# design.net
KiCad netlist of a schematic drawn in Altium Designer
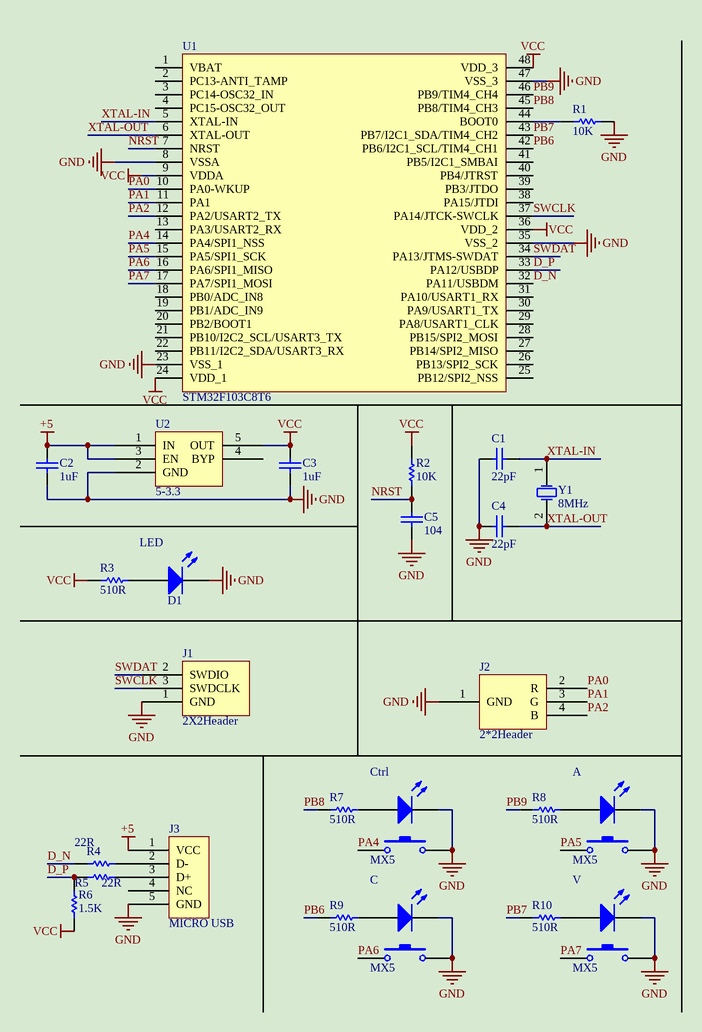
[diagram p0: 原理图.SchDoc]

(export (version "E")
  (design (tool "Eeschema 10.0.6"))
  (components
    (comp (ref "A") (value "MX5") (footprint "Key") (libsource (lib "Keyboard") (part "Key")))
    (comp (ref "C") (value "MX5") (footprint "Key") (libsource (lib "Keyboard") (part "Key")))
    (comp (ref "C1")
      (value "22pF")
      (footprint "LC-1206_C")
      (description "Capacitor")
      (fields (field (name "PUBLISHER") "Altium Limited"))
      (libsource (lib "Keyboard") (part "Capacitor"))
    )
    (comp (ref "C2")
      (value "1uF")
      (footprint "LC-1206_C")
      (description "Capacitor")
      (fields (field (name "PUBLISHER") "Altium Limited"))
      (libsource (lib "Keyboard") (part "Capacitor"))
    )
    (comp (ref "C3")
      (value "1uF")
      (footprint "LC-1206_C")
      (description "Capacitor")
      (fields (field (name "PUBLISHER") "Altium Limited"))
      (libsource (lib "Keyboard") (part "Capacitor"))
    )
    (comp (ref "C4")
      (value "22pF")
      (footprint "LC-1206_C")
      (description "Capacitor")
      (fields (field (name "PUBLISHER") "Altium Limited"))
      (libsource (lib "Keyboard") (part "Capacitor"))
    )
    (comp (ref "C5")
      (value "104")
      (footprint "LC-1206_C")
      (description "Capacitor")
      (fields (field (name "PUBLISHER") "Altium Limited"))
      (libsource (lib "Keyboard") (part "Capacitor"))
    )
    (comp (ref "Ctrl") (value "MX5") (footprint "Key") (libsource (lib "Keyboard") (part "Key")))
    (comp (ref "D1")
      (value "LED")
      (footprint "LC-0603_LED_S3")
      (description "Typical INFRARED GaAs LED")
      (fields (field (name "PUBLISHER") "Altium Limited"))
      (libsource (lib "Keyboard") (part "LED"))
    )
    (comp (ref "J1") (value "2X2Header") (footprint "IDE3") (libsource (lib "Keyboard") (part "J-Link")))
    (comp (ref "J2")
      (value "2*2Header")
      (footprint "IDE4_2.54")
      (libsource (lib "Keyboard") (part "RGB_LED"))
    )
    (comp (ref "J3") (value "MICRO USB") (footprint "Micro_USB") (libsource (lib "Keyboard") (part "USB")))
    (comp (ref "R1")
      (value "10K")
      (footprint "LC-1206_R")
      (description "Resistor")
      (fields (field (name "PUBLISHER") "Altium Limited"))
      (libsource (lib "Keyboard") (part "Resistor"))
    )
    (comp (ref "R2")
      (value "10K")
      (footprint "LC-1206_R")
      (description "Resistor")
      (fields (field (name "PUBLISHER") "Altium Limited"))
      (libsource (lib "Keyboard") (part "Resistor"))
    )
    (comp (ref "R3")
      (value "510R")
      (footprint "LC-1206_R")
      (description "Resistor")
      (fields (field (name "PUBLISHER") "Altium Limited"))
      (libsource (lib "Keyboard") (part "Resistor"))
    )
    (comp (ref "R4")
      (value "22R")
      (footprint "LC-1206_R")
      (description "Resistor")
      (fields (field (name "PUBLISHER") "Altium Limited"))
      (libsource (lib "Keyboard") (part "Resistor"))
    )
    (comp (ref "R5")
      (value "22R")
      (footprint "LC-1206_R")
      (description "Resistor")
      (fields (field (name "PUBLISHER") "Altium Limited"))
      (libsource (lib "Keyboard") (part "Resistor"))
    )
    (comp (ref "R6")
      (value "1.5K")
      (footprint "LC-1206_R")
      (description "Resistor")
      (fields (field (name "PUBLISHER") "Altium Limited"))
      (libsource (lib "Keyboard") (part "Resistor"))
    )
    (comp (ref "R7")
      (value "510R")
      (footprint "LC-1206_R")
      (description "Resistor")
      (fields (field (name "PUBLISHER") "Altium Limited"))
      (libsource (lib "Keyboard") (part "Resistor"))
    )
    (comp (ref "R8")
      (value "510R")
      (footprint "LC-1206_R")
      (description "Resistor")
      (fields (field (name "PUBLISHER") "Altium Limited"))
      (libsource (lib "Keyboard") (part "Resistor"))
    )
    (comp (ref "R9")
      (value "510R")
      (footprint "LC-1206_R")
      (description "Resistor")
      (fields (field (name "PUBLISHER") "Altium Limited"))
      (libsource (lib "Keyboard") (part "Resistor"))
    )
    (comp (ref "R10")
      (value "510R")
      (footprint "LC-1206_R")
      (description "Resistor")
      (fields (field (name "PUBLISHER") "Altium Limited"))
      (libsource (lib "Keyboard") (part "Resistor"))
    )
    (comp (ref "U1")
      (value "STM32F103C8T6")
      (footprint "lqfp48")
      (libsource (lib "Keyboard") (part "STM32F103C8T6"))
    )
    (comp (ref "U2")
      (value "5-3.3")
      (footprint "LC-SOT-23-5")
      (description "SPX3819")
      (libsource (lib "Keyboard") (part "SPX3819"))
    )
    (comp (ref "V") (value "MX5") (footprint "Key") (libsource (lib "Keyboard") (part "Key")))
    (comp (ref "Y1")
      (value "8MHz")
      (footprint "LC-HC-49S")
      (description "Crystal Oscillator")
      (fields (field (name "PUBLISHER") "Altium Limited"))
      (libsource (lib "Keyboard") (part "XTAL"))
    )
  )
  (nets
    (net (code "1") (name "+5") (class "Default")
      (node (ref "C2") (pin "2") (pinfunction "2_2") (pintype "passive"))
      (node (ref "J3") (pin "1") (pinfunction "VCC_1") (pintype "passive"))
      (node (ref "U2") (pin "1") (pinfunction "IN_1") (pintype "passive"))
      (node (ref "U2") (pin "3") (pinfunction "EN_3") (pintype "passive"))
    )
    (net (code "2") (name "/D_N") (class "Default")
      (node (ref "R4") (pin "1") (pinfunction "1_1") (pintype "passive"))
      (node (ref "U1") (pin "32") (pinfunction "PA11/USBDM_32") (pintype "passive"))
    )
    (net (code "3") (name "/D_P") (class "Default")
      (node (ref "R5") (pin "1") (pinfunction "1_1") (pintype "passive"))
      (node (ref "R6") (pin "2") (pinfunction "2_2") (pintype "passive"))
      (node (ref "U1") (pin "33") (pinfunction "PA12/USBDP_33") (pintype "passive"))
    )
    (net (code "4") (name "/NRST") (class "Default")
      (node (ref "C5") (pin "2") (pinfunction "2_2") (pintype "passive"))
      (node (ref "R2") (pin "1") (pinfunction "1_1") (pintype "passive"))
      (node (ref "U1") (pin "7") (pinfunction "NRST_7") (pintype "passive"))
    )
    (net (code "5") (name "/PA0") (class "Default")
      (node (ref "J2") (pin "2") (pinfunction "R_2") (pintype "passive"))
      (node (ref "U1") (pin "10") (pinfunction "PA0-WKUP_10") (pintype "passive"))
    )
    (net (code "6") (name "/PA1") (class "Default")
      (node (ref "J2") (pin "3") (pinfunction "G_3") (pintype "passive"))
      (node (ref "U1") (pin "11") (pinfunction "PA1_11") (pintype "passive"))
    )
    (net (code "7") (name "/PA2") (class "Default")
      (node (ref "J2") (pin "4") (pinfunction "B_4") (pintype "passive"))
      (node (ref "U1") (pin "12") (pinfunction "PA2/USART2_TX_12") (pintype "passive"))
    )
    (net (code "8") (name "/PA4") (class "Default")
      (node (ref "Ctrl") (pin "1") (pinfunction "1_1") (pintype "passive"))
      (node (ref "U1") (pin "14") (pinfunction "PA4/SPI1_NSS_14") (pintype "passive"))
    )
    (net (code "9") (name "/PA5") (class "Default")
      (node (ref "A") (pin "1") (pinfunction "1_1") (pintype "passive"))
      (node (ref "U1") (pin "15") (pinfunction "PA5/SPI1_SCK_15") (pintype "passive"))
    )
    (net (code "10") (name "/PA6") (class "Default")
      (node (ref "C") (pin "1") (pinfunction "1_1") (pintype "passive"))
      (node (ref "U1") (pin "16") (pinfunction "PA6/SPI1_MISO_16") (pintype "passive"))
    )
    (net (code "11") (name "/PA7") (class "Default")
      (node (ref "U1") (pin "17") (pinfunction "PA7/SPI1_MOSI_17") (pintype "passive"))
      (node (ref "V") (pin "1") (pinfunction "1_1") (pintype "passive"))
    )
    (net (code "12") (name "/PB6") (class "Default")
      (node (ref "R9") (pin "1") (pinfunction "1_1") (pintype "passive"))
      (node (ref "U1") (pin "42") (pinfunction "PB6/I2C1_SCL/TIM4_CH1_42") (pintype "passive"))
    )
    (net (code "13") (name "/PB7") (class "Default")
      (node (ref "R10") (pin "1") (pinfunction "1_1") (pintype "passive"))
      (node (ref "U1") (pin "43") (pinfunction "PB7/I2C1_SDA/TIM4_CH2_43") (pintype "passive"))
    )
    (net (code "14") (name "/PB8") (class "Default")
      (node (ref "R7") (pin "1") (pinfunction "1_1") (pintype "passive"))
      (node (ref "U1") (pin "45") (pinfunction "PB8/TIM4_CH3_45") (pintype "passive"))
    )
    (net (code "15") (name "/PB9") (class "Default")
      (node (ref "R8") (pin "1") (pinfunction "1_1") (pintype "passive"))
      (node (ref "U1") (pin "46") (pinfunction "PB9/TIM4_CH4_46") (pintype "passive"))
    )
    (net (code "16") (name "/SWCLK") (class "Default")
      (node (ref "J1") (pin "3") (pinfunction "SWDCLK_3") (pintype "passive"))
      (node (ref "U1") (pin "37") (pinfunction "PA14/JTCK-SWCLK_37") (pintype "passive"))
    )
    (net (code "17") (name "/SWDAT") (class "Default")
      (node (ref "J1") (pin "2") (pinfunction "SWDIO_2") (pintype "passive"))
      (node (ref "U1") (pin "34") (pinfunction "PA13/JTMS-SWDAT_34") (pintype "passive"))
    )
    (net (code "18") (name "/XTAL-IN") (class "Default")
      (node (ref "C1") (pin "2") (pinfunction "2_2") (pintype "passive"))
      (node (ref "U1") (pin "5") (pinfunction "XTAL-IN_5") (pintype "passive"))
      (node (ref "Y1") (pin "1") (pinfunction "OSC1_1") (pintype "passive"))
    )
    (net (code "19") (name "/XTAL-OUT") (class "Default")
      (node (ref "C4") (pin "2") (pinfunction "2_2") (pintype "passive"))
      (node (ref "U1") (pin "6") (pinfunction "XTAL-OUT_6") (pintype "passive"))
      (node (ref "Y1") (pin "2") (pinfunction "OSC2_2") (pintype "passive"))
    )
    (net (code "20") (name "GND") (class "Default")
      (node (ref "A") (pin "2") (pinfunction "2_2") (pintype "passive"))
      (node (ref "A") (pin "K") (pinfunction "K_K") (pintype "passive"))
      (node (ref "C") (pin "2") (pinfunction "2_2") (pintype "passive"))
      (node (ref "C") (pin "K") (pinfunction "K_K") (pintype "passive"))
      (node (ref "C1") (pin "1") (pinfunction "1_1") (pintype "passive"))
      (node (ref "C2") (pin "1") (pinfunction "1_1") (pintype "passive"))
      (node (ref "C3") (pin "1") (pinfunction "1_1") (pintype "passive"))
      (node (ref "C4") (pin "1") (pinfunction "1_1") (pintype "passive"))
      (node (ref "C5") (pin "1") (pinfunction "1_1") (pintype "passive"))
      (node (ref "Ctrl") (pin "2") (pinfunction "2_2") (pintype "passive"))
      (node (ref "Ctrl") (pin "K") (pinfunction "K_K") (pintype "passive"))
      (node (ref "D1") (pin "K") (pinfunction "2_K") (pintype "passive"))
      (node (ref "J1") (pin "1") (pinfunction "GND_1") (pintype "passive"))
      (node (ref "J2") (pin "1") (pinfunction "GND_1") (pintype "passive"))
      (node (ref "J3") (pin "5") (pinfunction "GND_5") (pintype "passive"))
      (node (ref "R1") (pin "2") (pinfunction "2_2") (pintype "passive"))
      (node (ref "U1") (pin "23") (pinfunction "VSS_1_23") (pintype "passive"))
      (node (ref "U1") (pin "35") (pinfunction "VSS_2_35") (pintype "passive"))
      (node (ref "U1") (pin "47") (pinfunction "VSS_3_47") (pintype "passive"))
      (node (ref "U1") (pin "8") (pinfunction "VSSA_8") (pintype "passive"))
      (node (ref "U2") (pin "2") (pinfunction "GND_2") (pintype "passive"))
      (node (ref "V") (pin "2") (pinfunction "2_2") (pintype "passive"))
      (node (ref "V") (pin "K") (pinfunction "K_K") (pintype "passive"))
    )
    (net (code "21") (name "Net-(A-PadA)") (class "Default")
      (node (ref "A") (pin "A") (pinfunction "A_A") (pintype "passive"))
      (node (ref "R8") (pin "2") (pinfunction "2_2") (pintype "passive"))
    )
    (net (code "22") (name "Net-(C-PadA)") (class "Default")
      (node (ref "C") (pin "A") (pinfunction "A_A") (pintype "passive"))
      (node (ref "R9") (pin "2") (pinfunction "2_2") (pintype "passive"))
    )
    (net (code "23") (name "Net-(Ctrl-PadA)") (class "Default")
      (node (ref "Ctrl") (pin "A") (pinfunction "A_A") (pintype "passive"))
      (node (ref "R7") (pin "2") (pinfunction "2_2") (pintype "passive"))
    )
    (net (code "24") (name "Net-(D1-1)") (class "Default")
      (node (ref "D1") (pin "A") (pinfunction "1_A") (pintype "passive"))
      (node (ref "R3") (pin "2") (pinfunction "2_2") (pintype "passive"))
    )
    (net (code "25") (name "Net-(J3-D+)") (class "Default")
      (node (ref "J3") (pin "3") (pinfunction "D+_3") (pintype "passive"))
      (node (ref "R5") (pin "2") (pinfunction "2_2") (pintype "passive"))
    )
    (net (code "26") (name "Net-(J3-D-)") (class "Default")
      (node (ref "J3") (pin "2") (pinfunction "D-_2") (pintype "passive"))
      (node (ref "R4") (pin "2") (pinfunction "2_2") (pintype "passive"))
    )
    (net (code "27") (name "Net-(R10-Pad2)") (class "Default")
      (node (ref "R10") (pin "2") (pinfunction "2_2") (pintype "passive"))
      (node (ref "V") (pin "A") (pinfunction "A_A") (pintype "passive"))
    )
    (net (code "28") (name "Net-(U1-BOOT0)") (class "Default")
      (node (ref "R1") (pin "1") (pinfunction "1_1") (pintype "passive"))
      (node (ref "U1") (pin "44") (pinfunction "BOOT0_44") (pintype "passive"))
    )
    (net (code "29") (name "VCC") (class "Default")
      (node (ref "C3") (pin "2") (pinfunction "2_2") (pintype "passive"))
      (node (ref "R2") (pin "2") (pinfunction "2_2") (pintype "passive"))
      (node (ref "R3") (pin "1") (pinfunction "1_1") (pintype "passive"))
      (node (ref "R6") (pin "1") (pinfunction "1_1") (pintype "passive"))
      (node (ref "U1") (pin "24") (pinfunction "VDD_1_24") (pintype "passive"))
      (node (ref "U1") (pin "36") (pinfunction "VDD_2_36") (pintype "passive"))
      (node (ref "U1") (pin "48") (pinfunction "VDD_3_48") (pintype "passive"))
      (node (ref "U1") (pin "9") (pinfunction "VDDA_9") (pintype "passive"))
      (node (ref "U2") (pin "5") (pinfunction "OUT_5") (pintype "passive"))
    )
    (net (code "30") (name "unconnected-(J3-NC-Pad4)") (class "Default")
      (node (ref "J3") (pin "4") (pinfunction "NC_4") (pintype "passive"))
    )
    (net (code "31") (name "unconnected-(U1-PA3{slash}USART2_RX-Pad13)") (class "Default")
      (node (ref "U1") (pin "13") (pinfunction "PA3/USART2_RX_13") (pintype "passive"))
    )
    (net (code "32") (name "unconnected-(U1-PA8{slash}USART1_CLK-Pad29)") (class "Default")
      (node (ref "U1") (pin "29") (pinfunction "PA8/USART1_CLK_29") (pintype "passive"))
    )
    (net (code "33") (name "unconnected-(U1-PA9{slash}USART1_TX-Pad30)") (class "Default")
      (node (ref "U1") (pin "30") (pinfunction "PA9/USART1_TX_30") (pintype "passive"))
    )
    (net (code "34") (name "unconnected-(U1-PA10{slash}USART1_RX-Pad31)") (class "Default")
      (node (ref "U1") (pin "31") (pinfunction "PA10/USART1_RX_31") (pintype "passive"))
    )
    (net (code "35") (name "unconnected-(U1-PA15{slash}JTDI-Pad38)") (class "Default")
      (node (ref "U1") (pin "38") (pinfunction "PA15/JTDI_38") (pintype "passive"))
    )
    (net (code "36") (name "unconnected-(U1-PB0{slash}ADC_IN8-Pad18)") (class "Default")
      (node (ref "U1") (pin "18") (pinfunction "PB0/ADC_IN8_18") (pintype "passive"))
    )
    (net (code "37") (name "unconnected-(U1-PB1{slash}ADC_IN9-Pad19)") (class "Default")
      (node (ref "U1") (pin "19") (pinfunction "PB1/ADC_IN9_19") (pintype "passive"))
    )
    (net (code "38") (name "unconnected-(U1-PB2{slash}BOOT1-Pad20)") (class "Default")
      (node (ref "U1") (pin "20") (pinfunction "PB2/BOOT1_20") (pintype "passive"))
    )
    (net (code "39") (name "unconnected-(U1-PB3{slash}JTDO-Pad39)") (class "Default")
      (node (ref "U1") (pin "39") (pinfunction "PB3/JTDO_39") (pintype "passive"))
    )
    (net (code "40") (name "unconnected-(U1-PB4{slash}JTRST-Pad40)") (class "Default")
      (node (ref "U1") (pin "40") (pinfunction "PB4/JTRST_40") (pintype "passive"))
    )
    (net (code "41") (name "unconnected-(U1-PB5{slash}I2C1_SMBAI-Pad41)") (class "Default")
      (node (ref "U1") (pin "41") (pinfunction "PB5/I2C1_SMBAI_41") (pintype "passive"))
    )
    (net (code "42") (name "unconnected-(U1-PB10{slash}I2C2_SCL{slash}USART3_TX-Pad21)") (class "Default")
      (node (ref "U1") (pin "21") (pinfunction "PB10/I2C2_SCL/USART3_TX_21") (pintype "passive"))
    )
    (net (code "43") (name "unconnected-(U1-PB11{slash}I2C2_SDA{slash}USART3_RX-Pad22)") (class "Default")
      (node (ref "U1") (pin "22") (pinfunction "PB11/I2C2_SDA/USART3_RX_22") (pintype "passive"))
    )
    (net (code "44") (name "unconnected-(U1-PB12{slash}SPI2_NSS-Pad25)") (class "Default")
      (node (ref "U1") (pin "25") (pinfunction "PB12/SPI2_NSS_25") (pintype "passive"))
    )
    (net (code "45") (name "unconnected-(U1-PB13{slash}SPI2_SCK-Pad26)") (class "Default")
      (node (ref "U1") (pin "26") (pinfunction "PB13/SPI2_SCK_26") (pintype "passive"))
    )
    (net (code "46") (name "unconnected-(U1-PB14{slash}SPI2_MISO-Pad27)") (class "Default")
      (node (ref "U1") (pin "27") (pinfunction "PB14/SPI2_MISO_27") (pintype "passive"))
    )
    (net (code "47") (name "unconnected-(U1-PB15{slash}SPI2_MOSI-Pad28)") (class "Default")
      (node (ref "U1") (pin "28") (pinfunction "PB15/SPI2_MOSI_28") (pintype "passive"))
    )
    (net (code "48") (name "unconnected-(U1-PC13-ANTI_TAMP-Pad2)") (class "Default")
      (node (ref "U1") (pin "2") (pinfunction "PC13-ANTI_TAMP_2") (pintype "passive"))
    )
    (net (code "49") (name "unconnected-(U1-PC14-OSC32_IN-Pad3)") (class "Default")
      (node (ref "U1") (pin "3") (pinfunction "PC14-OSC32_IN_3") (pintype "passive"))
    )
    (net (code "50") (name "unconnected-(U1-PC15-OSC32_OUT-Pad4)") (class "Default")
      (node (ref "U1") (pin "4") (pinfunction "PC15-OSC32_OUT_4") (pintype "passive"))
    )
    (net (code "51") (name "unconnected-(U1-VBAT-Pad1)") (class "Default")
      (node (ref "U1") (pin "1") (pinfunction "VBAT_1") (pintype "passive"))
    )
    (net (code "52") (name "unconnected-(U2-BYP-Pad4)") (class "Default")
      (node (ref "U2") (pin "4") (pinfunction "BYP_4") (pintype "passive"))
    )
  )
)
